# Sheet1.net
KiCad netlist of a schematic drawn in Altium Designer
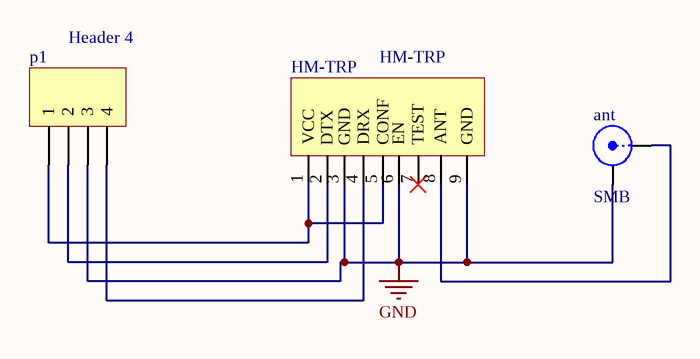
[diagram p0: Sheet1.SchDoc]

(export (version "E")
  (design (tool "Eeschema 10.0.6"))
  (components
    (comp (ref "ant")
      (value "SMB")
      (footprint "SMB_V-RJ45")
      (description "SMB Straight Connector")
      (fields (field (name "PUBLISHER") "Altium Limited"))
      (libsource (lib "Miscellaneous Connectors") (part "SMB"))
    )
    (comp (ref "HM-TRP")
      (value "HM-TRP")
      (footprint "hm-trp:PCBComponent_1")
      (libsource (lib "HM-TRP") (part "Component_1"))
    )
    (comp (ref "p1")
      (value "Header 4")
      (footprint "HDR1X4")
      (description "Header, 4-Pin")
      (fields (field (name "PUBLISHER") "Altium Limited"))
      (libsource (lib "Miscellaneous Connectors") (part "Header 4"))
    )
  )
  (nets
    (net (code "1") (name "GND") (class "Default")
      (node (ref "HM-TRP") (pin "3") (pinfunction "GND_3") (pintype "passive"))
      (node (ref "HM-TRP") (pin "6") (pinfunction "EN_6") (pintype "passive"))
      (node (ref "HM-TRP") (pin "9") (pinfunction "GND_9") (pintype "passive"))
      (node (ref "ant") (pin "2") (pinfunction "Y_2") (pintype "passive"))
      (node (ref "p1") (pin "3") (pinfunction "3_3") (pintype "passive"))
    )
    (net (code "2") (name "Net-(HM-TRP-ANT)") (class "Default")
      (node (ref "HM-TRP") (pin "8") (pinfunction "ANT_8") (pintype "passive"))
      (node (ref "ant") (pin "1") (pinfunction "X_1") (pintype "passive"))
    )
    (net (code "3") (name "Net-(HM-TRP-CONF)") (class "Default")
      (node (ref "HM-TRP") (pin "1") (pinfunction "VCC_1") (pintype "passive"))
      (node (ref "HM-TRP") (pin "5") (pinfunction "CONF_5") (pintype "passive"))
      (node (ref "p1") (pin "1") (pinfunction "1_1") (pintype "passive"))
    )
    (net (code "4") (name "Net-(HM-TRP-DRX)") (class "Default")
      (node (ref "HM-TRP") (pin "4") (pinfunction "DRX_4") (pintype "passive"))
      (node (ref "p1") (pin "4") (pinfunction "4_4") (pintype "passive"))
    )
    (net (code "5") (name "Net-(HM-TRP-DTX)") (class "Default")
      (node (ref "HM-TRP") (pin "2") (pinfunction "DTX_2") (pintype "passive"))
      (node (ref "p1") (pin "2") (pinfunction "2_2") (pintype "passive"))
    )
    (net (code "6") (name "unconnected-(HM-TRP-GND-Pad9)") (class "Default")
      (node (ref "HM-TRP") (pin "9") (pinfunction "GND_9") (pintype "passive"))
    )
    (net (code "7") (name "unconnected-(HM-TRP-TEST-Pad7)") (class "Default")
      (node (ref "HM-TRP") (pin "7") (pinfunction "TEST_7") (pintype "passive"))
    )
  )
)
